# CAN_Breakout.net
KiCad netlist of a schematic drawn in Altium Designer
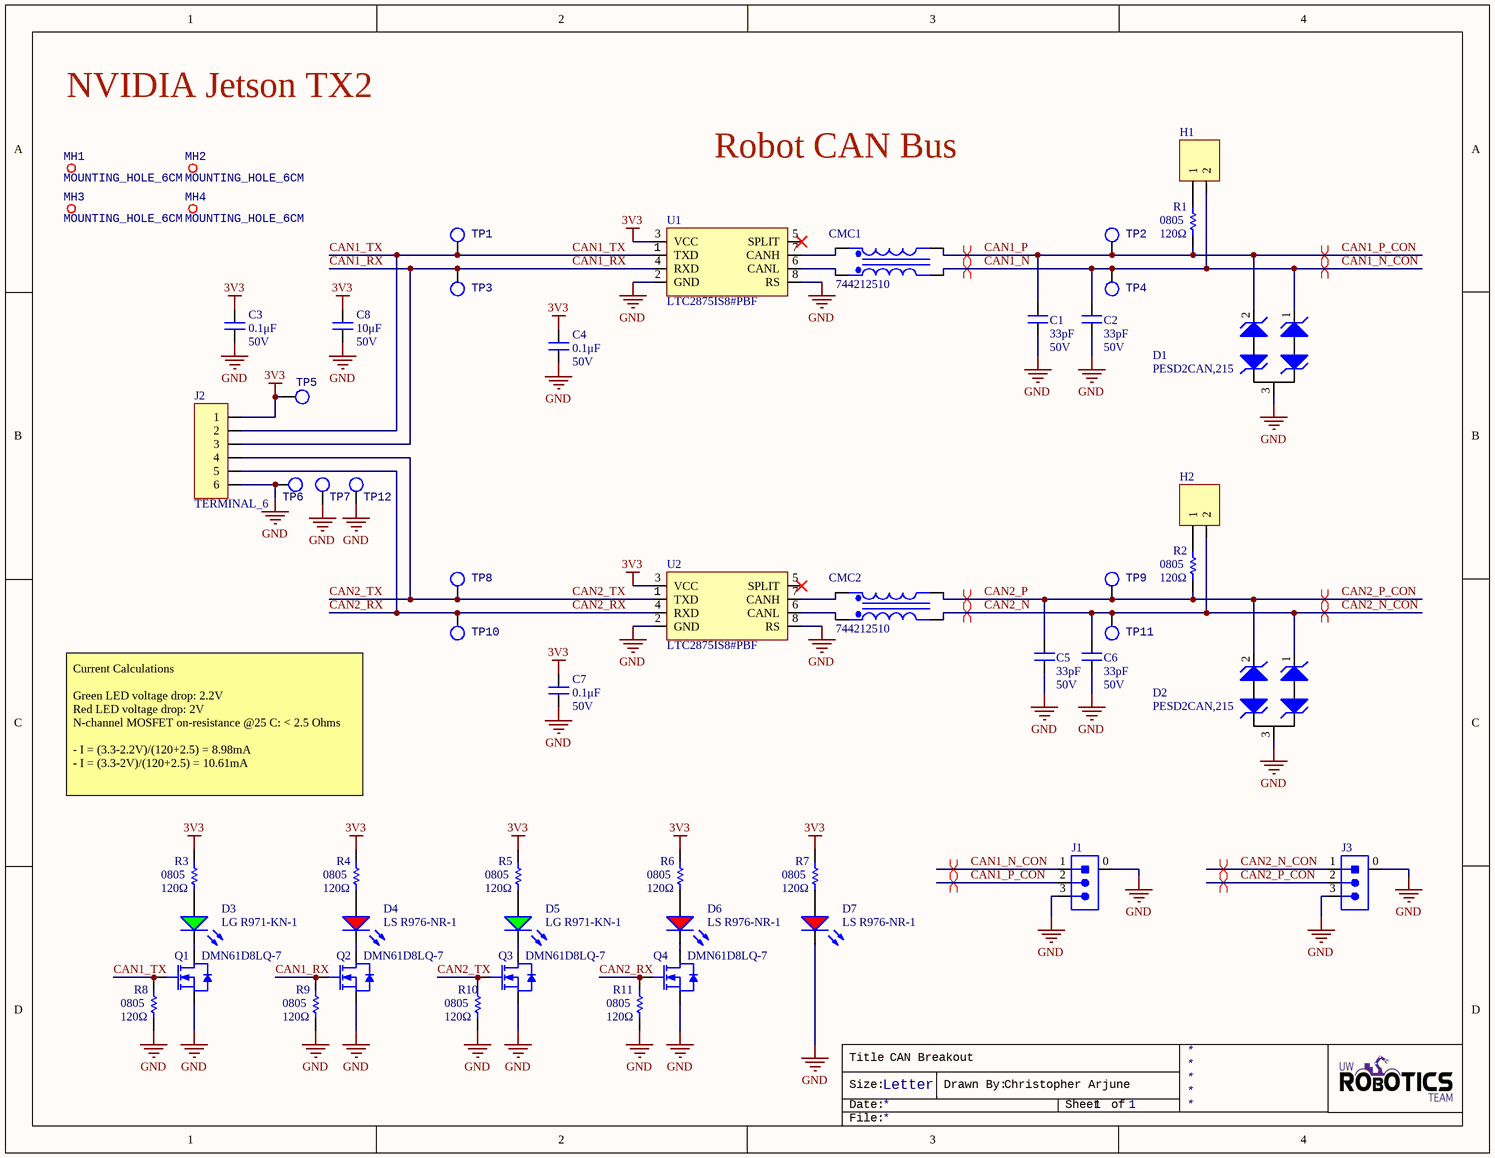
[diagram p0: CAN Breakout.SchDoc]

(export (version "E")
  (design (tool "Eeschema 10.0.6"))
  (components
    (comp (ref "C1")
      (value "33pF")
      (footprint "CAPC0603(1608)55_N")
      (description "CAP CER 33PF 50V C0G/NP0")
      (fields
        (field (name "TOLERANCE") "5%")
        (field (name "VOLTAGE") "50V")
        (field (name "Comment") "CAP_33pF_50V_0603")
      )
      (libsource (lib "UWRT_Schematic_Library_2020") (part "CAP_33pF_50V_0603"))
    )
    (comp (ref "C2")
      (value "33pF")
      (footprint "CAPC0603(1608)55_N")
      (description "CAP CER 33PF 50V C0G/NP0")
      (fields
        (field (name "TOLERANCE") "5%")
        (field (name "VOLTAGE") "50V")
        (field (name "Comment") "CAP_33pF_50V_0603")
      )
      (libsource (lib "UWRT_Schematic_Library_2020") (part "CAP_33pF_50V_0603"))
    )
    (comp (ref "C3")
      (value "0.1μF")
      (footprint "CAPC2012X140N")
      (description "CAP CER 0.1UF 50V X7R 0805")
      (fields (field (name "VOLTAGE RATING") "50V") (field (name "TOLERANCE") "10%"))
      (libsource (lib "UWRT_Schematic_Library_2020") (part "CAP_0.1uF_50V_0805"))
    )
    (comp (ref "C4")
      (value "0.1μF")
      (footprint "CAPC2012X140N")
      (description "CAP CER 0.1UF 50V X7R 0805")
      (fields (field (name "VOLTAGE RATING") "50V") (field (name "TOLERANCE") "10%"))
      (libsource (lib "UWRT_Schematic_Library_2020") (part "CAP_0.1uF_50V_0805"))
    )
    (comp (ref "C5")
      (value "33pF")
      (footprint "CAPC0603(1608)55_N")
      (description "CAP CER 33PF 50V C0G/NP0")
      (fields
        (field (name "TOLERANCE") "5%")
        (field (name "VOLTAGE") "50V")
        (field (name "Comment") "CAP_33pF_50V_0603")
      )
      (libsource (lib "UWRT_Schematic_Library_2020") (part "CAP_33pF_50V_0603"))
    )
    (comp (ref "C6")
      (value "33pF")
      (footprint "CAPC0603(1608)55_N")
      (description "CAP CER 33PF 50V C0G/NP0")
      (fields
        (field (name "TOLERANCE") "5%")
        (field (name "VOLTAGE") "50V")
        (field (name "Comment") "CAP_33pF_50V_0603")
      )
      (libsource (lib "UWRT_Schematic_Library_2020") (part "CAP_33pF_50V_0603"))
    )
    (comp (ref "C7")
      (value "0.1μF")
      (footprint "CAPC2012X140N")
      (description "CAP CER 0.1UF 50V X7R 0805")
      (fields (field (name "VOLTAGE RATING") "50V") (field (name "TOLERANCE") "10%"))
      (libsource (lib "UWRT_Schematic_Library_2020") (part "CAP_0.1uF_50V_0805"))
    )
    (comp (ref "C8")
      (value "10μF")
      (footprint "CAPC1206(3216)")
      (description "CAP CER 10UF 50V X5R 1206")
      (fields (field (name "VOLTAGE RATING") "50V") (field (name "Comment") "10uF"))
      (libsource (lib "UWRT_Schematic_Library_2020") (part "CAP_10uF_50V_1206"))
    )
    (comp (ref "CMC1")
      (value "*")
      (footprint "744212510")
      (description "CMC 51uH 300MA 2LN SMD")
      (fields (field (name "TOLERANCE") "50%") (field (name "MANUFACTURER PART NUMBER 1") "744212510"))
      (libsource (lib "UWRT_Schematic_Library_2020") (part "CMC_51uH"))
    )
    (comp (ref "CMC2")
      (value "*")
      (footprint "744212510")
      (description "CMC 51uH 300MA 2LN SMD")
      (fields (field (name "TOLERANCE") "50%") (field (name "MANUFACTURER PART NUMBER 1") "744212510"))
      (libsource (lib "UWRT_Schematic_Library_2020") (part "CMC_51uH"))
    )
    (comp (ref "D1")
      (value "TVS_DIODE_CAN")
      (footprint "TVS_DIODE_CAN")
      (description "TVS DIODE 24V 41V SOT323-3")
      (fields (field (name "MANUFACTURER PART NUMBER 1") "PESD2CAN,215"))
      (libsource (lib "UWRT_Schematic_Library_2020") (part "TVS_DIODE_CAN"))
    )
    (comp (ref "D2")
      (value "TVS_DIODE_CAN")
      (footprint "TVS_DIODE_CAN")
      (description "TVS DIODE 24V 41V SOT323-3")
      (fields (field (name "MANUFACTURER PART NUMBER 1") "PESD2CAN,215"))
      (libsource (lib "UWRT_Schematic_Library_2020") (part "TVS_DIODE_CAN"))
    )
    (comp (ref "D3")
      (value "LG R971-KN-1")
      (footprint "LED_0805_LINE")
      (description "LED GREEN DIFFUSED 0805 SMD")
      (libsource (lib "UWRT_Schematic_Library_2020") (part "DIO_LED_G"))
    )
    (comp (ref "D4")
      (value "LS R976-NR-1")
      (footprint "LED_0805_LINE")
      (description "LED RED DIFFUSED 0805 SMD")
      (libsource (lib "UWRT_Schematic_Library_2020") (part "DIO_LED_R"))
    )
    (comp (ref "D5")
      (value "LG R971-KN-1")
      (footprint "LED_0805_LINE")
      (description "LED GREEN DIFFUSED 0805 SMD")
      (libsource (lib "UWRT_Schematic_Library_2020") (part "DIO_LED_G"))
    )
    (comp (ref "D6")
      (value "LS R976-NR-1")
      (footprint "LED_0805_LINE")
      (description "LED RED DIFFUSED 0805 SMD")
      (libsource (lib "UWRT_Schematic_Library_2020") (part "DIO_LED_R"))
    )
    (comp (ref "D7")
      (value "LS R976-NR-1")
      (footprint "LED_0805_LINE")
      (description "LED RED DIFFUSED 0805 SMD")
      (libsource (lib "UWRT_Schematic_Library_2020") (part "DIO_LED_R"))
    )
    (comp (ref "H1")
      (value "JUMPER_2")
      (footprint "HDR1X2")
      (description "HEADER 2X1")
      (libsource (lib "UWRT_Schematic_Library_2020") (part "JUMPER_2"))
    )
    (comp (ref "H2")
      (value "JUMPER_2")
      (footprint "HDR1X2")
      (description "HEADER 2X1")
      (libsource (lib "UWRT_Schematic_Library_2020") (part "JUMPER_2"))
    )
    (comp (ref "J1")
      (value "*")
      (footprint "MOLEX-5025850370")
      (description "CONN RCPT 3POS 0.059 TIN SMD R/A")
      (libsource (lib "*") (part "CON_3M_SM_RA"))
    )
    (comp (ref "J2")
      (value "TERMINAL_6")
      (footprint "OSTYK51106030")
      (description "Header, 6-Pin")
      (libsource (lib "UWRT_Schematic_Library_2020") (part "TERMINAL_6"))
    )
    (comp (ref "J3")
      (value "*")
      (footprint "MOLEX-5025850370")
      (description "CONN RCPT 3POS 0.059 TIN SMD R/A")
      (libsource (lib "*") (part "CON_3M_SM_RA"))
    )
    (comp (ref "MH1")
      (value "MOUNTING_HOLE_6CM")
      (footprint "MOUNTING_HOLE")
      (libsource (lib "UWRT_Schematic_Library_2020") (part "MOUNTING_HOLE_6CM"))
    )
    (comp (ref "MH2")
      (value "MOUNTING_HOLE_6CM")
      (footprint "MOUNTING_HOLE")
      (libsource (lib "UWRT_Schematic_Library_2020") (part "MOUNTING_HOLE_6CM"))
    )
    (comp (ref "MH3")
      (value "MOUNTING_HOLE_6CM")
      (footprint "MOUNTING_HOLE")
      (libsource (lib "UWRT_Schematic_Library_2020") (part "MOUNTING_HOLE_6CM"))
    )
    (comp (ref "MH4")
      (value "MOUNTING_HOLE_6CM")
      (footprint "MOUNTING_HOLE")
      (libsource (lib "UWRT_Schematic_Library_2020") (part "MOUNTING_HOLE_6CM"))
    )
    (comp (ref "Q1")
      (value "NMOS_60V_470mA")
      (footprint "SOT23-3")
      (description "MOSFET N-CH 60V SOT23")
      (fields (field (name "MANUFACTURER PART NUMBER 1") "DMN61D8LQ-7"))
      (libsource (lib "UWRT_Schematic_Library_2020") (part "NMOS_60V_470mA"))
    )
    (comp (ref "Q2")
      (value "NMOS_60V_470mA")
      (footprint "SOT23-3")
      (description "MOSFET N-CH 60V SOT23")
      (fields (field (name "MANUFACTURER PART NUMBER 1") "DMN61D8LQ-7"))
      (libsource (lib "UWRT_Schematic_Library_2020") (part "NMOS_60V_470mA"))
    )
    (comp (ref "Q3")
      (value "NMOS_60V_470mA")
      (footprint "SOT23-3")
      (description "MOSFET N-CH 60V SOT23")
      (fields (field (name "MANUFACTURER PART NUMBER 1") "DMN61D8LQ-7"))
      (libsource (lib "UWRT_Schematic_Library_2020") (part "NMOS_60V_470mA"))
    )
    (comp (ref "Q4")
      (value "NMOS_60V_470mA")
      (footprint "SOT23-3")
      (description "MOSFET N-CH 60V SOT23")
      (fields (field (name "MANUFACTURER PART NUMBER 1") "DMN61D8LQ-7"))
      (libsource (lib "UWRT_Schematic_Library_2020") (part "NMOS_60V_470mA"))
    )
    (comp (ref "R1")
      (value "120")
      (footprint "RESC2012X60N")
      (description "RES SMD 120 OHM 1% 1/8W 0805")
      (fields (field (name "CASE CODE (IMPERIAL)") "0805") (field (name "RESISTANCE") "120Ω"))
      (libsource (lib "UWRT_Schematic_Library_2020") (part "RES_120Ω_0805"))
    )
    (comp (ref "R2")
      (value "120")
      (footprint "RESC2012X60N")
      (description "RES SMD 120 OHM 1% 1/8W 0805")
      (fields (field (name "CASE CODE (IMPERIAL)") "0805") (field (name "RESISTANCE") "120Ω"))
      (libsource (lib "UWRT_Schematic_Library_2020") (part "RES_120Ω_0805"))
    )
    (comp (ref "R3")
      (value "120")
      (footprint "RESC2012X60N")
      (description "RES SMD 120 OHM 1% 1/8W 0805")
      (fields (field (name "CASE CODE (IMPERIAL)") "0805") (field (name "RESISTANCE") "120Ω"))
      (libsource (lib "UWRT_Schematic_Library_2020") (part "RES_120Ω_0805"))
    )
    (comp (ref "R4")
      (value "120")
      (footprint "RESC2012X60N")
      (description "RES SMD 120 OHM 1% 1/8W 0805")
      (fields (field (name "CASE CODE (IMPERIAL)") "0805") (field (name "RESISTANCE") "120Ω"))
      (libsource (lib "UWRT_Schematic_Library_2020") (part "RES_120Ω_0805"))
    )
    (comp (ref "R5")
      (value "120")
      (footprint "RESC2012X60N")
      (description "RES SMD 120 OHM 1% 1/8W 0805")
      (fields (field (name "CASE CODE (IMPERIAL)") "0805") (field (name "RESISTANCE") "120Ω"))
      (libsource (lib "UWRT_Schematic_Library_2020") (part "RES_120Ω_0805"))
    )
    (comp (ref "R6")
      (value "120")
      (footprint "RESC2012X60N")
      (description "RES SMD 120 OHM 1% 1/8W 0805")
      (fields (field (name "CASE CODE (IMPERIAL)") "0805") (field (name "RESISTANCE") "120Ω"))
      (libsource (lib "UWRT_Schematic_Library_2020") (part "RES_120Ω_0805"))
    )
    (comp (ref "R7")
      (value "120")
      (footprint "RESC2012X60N")
      (description "RES SMD 120 OHM 1% 1/8W 0805")
      (fields (field (name "CASE CODE (IMPERIAL)") "0805") (field (name "RESISTANCE") "120Ω"))
      (libsource (lib "UWRT_Schematic_Library_2020") (part "RES_120Ω_0805"))
    )
    (comp (ref "R8")
      (value "120")
      (footprint "RESC2012X60N")
      (description "RES SMD 120 OHM 1% 1/8W 0805")
      (fields (field (name "CASE CODE (IMPERIAL)") "0805") (field (name "RESISTANCE") "120Ω"))
      (libsource (lib "UWRT_Schematic_Library_2020") (part "RES_120Ω_0805"))
    )
    (comp (ref "R9")
      (value "120")
      (footprint "RESC2012X60N")
      (description "RES SMD 120 OHM 1% 1/8W 0805")
      (fields (field (name "CASE CODE (IMPERIAL)") "0805") (field (name "RESISTANCE") "120Ω"))
      (libsource (lib "UWRT_Schematic_Library_2020") (part "RES_120Ω_0805"))
    )
    (comp (ref "R10")
      (value "120")
      (footprint "RESC2012X60N")
      (description "RES SMD 120 OHM 1% 1/8W 0805")
      (fields (field (name "CASE CODE (IMPERIAL)") "0805") (field (name "RESISTANCE") "120Ω"))
      (libsource (lib "UWRT_Schematic_Library_2020") (part "RES_120Ω_0805"))
    )
    (comp (ref "R11")
      (value "120")
      (footprint "RESC2012X60N")
      (description "RES SMD 120 OHM 1% 1/8W 0805")
      (fields (field (name "CASE CODE (IMPERIAL)") "0805") (field (name "RESISTANCE") "120Ω"))
      (libsource (lib "UWRT_Schematic_Library_2020") (part "RES_120Ω_0805"))
    )
    (comp (ref "TP1")
      (value "TESTPOINT_LOOP")
      (footprint "TESTPOINT_LOOP")
      (description "PC TEST POINT MINIATURE WHITE")
      (libsource (lib "UWRT_Schematic_Library_2020") (part "TESTPOINT_LOOP"))
    )
    (comp (ref "TP2")
      (value "TESTPOINT_LOOP")
      (footprint "TESTPOINT_LOOP")
      (description "PC TEST POINT MINIATURE WHITE")
      (libsource (lib "UWRT_Schematic_Library_2020") (part "TESTPOINT_LOOP"))
    )
    (comp (ref "TP3")
      (value "TESTPOINT_LOOP")
      (footprint "TESTPOINT_LOOP")
      (description "PC TEST POINT MINIATURE WHITE")
      (libsource (lib "UWRT_Schematic_Library_2020") (part "TESTPOINT_LOOP"))
    )
    (comp (ref "TP4")
      (value "TESTPOINT_LOOP")
      (footprint "TESTPOINT_LOOP")
      (description "PC TEST POINT MINIATURE WHITE")
      (libsource (lib "UWRT_Schematic_Library_2020") (part "TESTPOINT_LOOP"))
    )
    (comp (ref "TP5")
      (value "TESTPOINT_LOOP")
      (footprint "TESTPOINT_LOOP")
      (description "PC TEST POINT MINIATURE WHITE")
      (libsource (lib "UWRT_Schematic_Library_2020") (part "TESTPOINT_LOOP"))
    )
    (comp (ref "TP6")
      (value "TESTPOINT_LOOP")
      (footprint "TESTPOINT_LOOP")
      (description "PC TEST POINT MINIATURE WHITE")
      (libsource (lib "UWRT_Schematic_Library_2020") (part "TESTPOINT_LOOP"))
    )
    (comp (ref "TP7")
      (value "TESTPOINT_LOOP")
      (footprint "TESTPOINT_LOOP")
      (description "PC TEST POINT MINIATURE WHITE")
      (libsource (lib "UWRT_Schematic_Library_2020") (part "TESTPOINT_LOOP"))
    )
    (comp (ref "TP8")
      (value "TESTPOINT_LOOP")
      (footprint "TESTPOINT_LOOP")
      (description "PC TEST POINT MINIATURE WHITE")
      (libsource (lib "UWRT_Schematic_Library_2020") (part "TESTPOINT_LOOP"))
    )
    (comp (ref "TP9")
      (value "TESTPOINT_LOOP")
      (footprint "TESTPOINT_LOOP")
      (description "PC TEST POINT MINIATURE WHITE")
      (libsource (lib "UWRT_Schematic_Library_2020") (part "TESTPOINT_LOOP"))
    )
    (comp (ref "TP10")
      (value "TESTPOINT_LOOP")
      (footprint "TESTPOINT_LOOP")
      (description "PC TEST POINT MINIATURE WHITE")
      (libsource (lib "UWRT_Schematic_Library_2020") (part "TESTPOINT_LOOP"))
    )
    (comp (ref "TP11")
      (value "TESTPOINT_LOOP")
      (footprint "TESTPOINT_LOOP")
      (description "PC TEST POINT MINIATURE WHITE")
      (libsource (lib "UWRT_Schematic_Library_2020") (part "TESTPOINT_LOOP"))
    )
    (comp (ref "TP12")
      (value "TESTPOINT_LOOP")
      (footprint "TESTPOINT_LOOP")
      (description "PC TEST POINT MINIATURE WHITE")
      (libsource (lib "UWRT_Schematic_Library_2020") (part "TESTPOINT_LOOP"))
    )
    (comp (ref "U1")
      (value "IC TXRX CAN")
      (footprint "LT-S8_N")
      (description "IC TXRX CAN 4MBPS 8SO")
      (fields (field (name "MANUFACTURER PART NUMBER 1") "LTC2875IS8#PBF"))
      (libsource (lib "UWRT_Schematic_Library_2020") (part "LTC2875"))
    )
    (comp (ref "U2")
      (value "IC TXRX CAN")
      (footprint "LT-S8_N")
      (description "IC TXRX CAN 4MBPS 8SO")
      (fields (field (name "MANUFACTURER PART NUMBER 1") "LTC2875IS8#PBF"))
      (libsource (lib "UWRT_Schematic_Library_2020") (part "LTC2875"))
    )
  )
  (nets
    (net (code "1") (name "/CAN1_N") (class "Default")
      (node (ref "C2") (pin "2") (pinfunction "2_2") (pintype "passive"))
      (node (ref "CMC1") (pin "5") (pinfunction "Pri-_5") (pintype "passive"))
      (node (ref "D1") (pin "1") (pinfunction "1_1") (pintype "passive"))
      (node (ref "H1") (pin "2") (pinfunction "2_2") (pintype "passive"))
      (node (ref "J1") (pin "1") (pinfunction "1_1") (pintype "passive"))
      (node (ref "TP4") (pin "1") (pintype "passive"))
    )
    (net (code "2") (name "/CAN1_P") (class "Default")
      (node (ref "C1") (pin "2") (pinfunction "2_2") (pintype "passive"))
      (node (ref "CMC1") (pin "4") (pinfunction "Sec-_4") (pintype "passive"))
      (node (ref "D1") (pin "2") (pinfunction "2_2") (pintype "passive"))
      (node (ref "J1") (pin "2") (pinfunction "2_2") (pintype "passive"))
      (node (ref "R1") (pin "1") (pinfunction "1_1") (pintype "passive"))
      (node (ref "TP2") (pin "1") (pintype "passive"))
    )
    (net (code "3") (name "/CAN1_RX") (class "Default")
      (node (ref "J2") (pin "3") (pinfunction "3_3") (pintype "passive"))
      (node (ref "Q2") (pin "1") (pinfunction "GATE_1") (pintype "passive"))
      (node (ref "R9") (pin "2") (pinfunction "2_2") (pintype "passive"))
      (node (ref "TP3") (pin "1") (pintype "passive"))
      (node (ref "U1") (pin "4") (pinfunction "RXD_4") (pintype "passive"))
    )
    (net (code "4") (name "/CAN1_TX") (class "Default")
      (node (ref "J2") (pin "2") (pinfunction "2_2") (pintype "passive"))
      (node (ref "Q1") (pin "1") (pinfunction "GATE_1") (pintype "passive"))
      (node (ref "R8") (pin "2") (pinfunction "2_2") (pintype "passive"))
      (node (ref "TP1") (pin "1") (pintype "passive"))
      (node (ref "U1") (pin "1") (pinfunction "TXD_1") (pintype "passive"))
    )
    (net (code "5") (name "/CAN2_N") (class "Default")
      (node (ref "C6") (pin "2") (pinfunction "2_2") (pintype "passive"))
      (node (ref "CMC2") (pin "5") (pinfunction "Pri-_5") (pintype "passive"))
      (node (ref "D2") (pin "1") (pinfunction "1_1") (pintype "passive"))
      (node (ref "H2") (pin "2") (pinfunction "2_2") (pintype "passive"))
      (node (ref "J3") (pin "1") (pinfunction "1_1") (pintype "passive"))
      (node (ref "TP11") (pin "1") (pintype "passive"))
    )
    (net (code "6") (name "/CAN2_P") (class "Default")
      (node (ref "C5") (pin "2") (pinfunction "2_2") (pintype "passive"))
      (node (ref "CMC2") (pin "4") (pinfunction "Sec-_4") (pintype "passive"))
      (node (ref "D2") (pin "2") (pinfunction "2_2") (pintype "passive"))
      (node (ref "J3") (pin "2") (pinfunction "2_2") (pintype "passive"))
      (node (ref "R2") (pin "1") (pinfunction "1_1") (pintype "passive"))
      (node (ref "TP9") (pin "1") (pintype "passive"))
    )
    (net (code "7") (name "/CAN2_RX") (class "Default")
      (node (ref "J2") (pin "5") (pinfunction "5_5") (pintype "passive"))
      (node (ref "Q4") (pin "1") (pinfunction "GATE_1") (pintype "passive"))
      (node (ref "R11") (pin "2") (pinfunction "2_2") (pintype "passive"))
      (node (ref "TP10") (pin "1") (pintype "passive"))
      (node (ref "U2") (pin "4") (pinfunction "RXD_4") (pintype "passive"))
    )
    (net (code "8") (name "/CAN2_TX") (class "Default")
      (node (ref "J2") (pin "4") (pinfunction "4_4") (pintype "passive"))
      (node (ref "Q3") (pin "1") (pinfunction "GATE_1") (pintype "passive"))
      (node (ref "R10") (pin "2") (pinfunction "2_2") (pintype "passive"))
      (node (ref "TP8") (pin "1") (pintype "passive"))
      (node (ref "U2") (pin "1") (pinfunction "TXD_1") (pintype "passive"))
    )
    (net (code "9") (name "3V3") (class "Default")
      (node (ref "C3") (pin "2") (pinfunction "2_2") (pintype "passive"))
      (node (ref "C4") (pin "2") (pinfunction "2_2") (pintype "passive"))
      (node (ref "C7") (pin "2") (pinfunction "2_2") (pintype "passive"))
      (node (ref "C8") (pin "2") (pinfunction "2_2") (pintype "passive"))
      (node (ref "J2") (pin "1") (pinfunction "1_1") (pintype "passive"))
      (node (ref "R3") (pin "2") (pinfunction "2_2") (pintype "passive"))
      (node (ref "R4") (pin "2") (pinfunction "2_2") (pintype "passive"))
      (node (ref "R5") (pin "2") (pinfunction "2_2") (pintype "passive"))
      (node (ref "R6") (pin "2") (pinfunction "2_2") (pintype "passive"))
      (node (ref "R7") (pin "2") (pinfunction "2_2") (pintype "passive"))
      (node (ref "TP5") (pin "1") (pintype "passive"))
      (node (ref "U1") (pin "3") (pinfunction "VCC_3") (pintype "passive"))
      (node (ref "U2") (pin "3") (pinfunction "VCC_3") (pintype "passive"))
    )
    (net (code "10") (name "GND") (class "Default")
      (node (ref "C1") (pin "1") (pinfunction "1_1") (pintype "passive"))
      (node (ref "C2") (pin "1") (pinfunction "1_1") (pintype "passive"))
      (node (ref "C3") (pin "1") (pinfunction "1_1") (pintype "passive"))
      (node (ref "C4") (pin "1") (pinfunction "1_1") (pintype "passive"))
      (node (ref "C5") (pin "1") (pinfunction "1_1") (pintype "passive"))
      (node (ref "C6") (pin "1") (pinfunction "1_1") (pintype "passive"))
      (node (ref "C7") (pin "1") (pinfunction "1_1") (pintype "passive"))
      (node (ref "C8") (pin "1") (pinfunction "1_1") (pintype "passive"))
      (node (ref "D1") (pin "3") (pinfunction "3_3") (pintype "passive"))
      (node (ref "D2") (pin "3") (pinfunction "3_3") (pintype "passive"))
      (node (ref "D7") (pin "2") (pinfunction "K_2") (pintype "passive"))
      (node (ref "J1") (pin "0") (pinfunction "0_0") (pintype "passive"))
      (node (ref "J1") (pin "3") (pinfunction "3_3") (pintype "passive"))
      (node (ref "J2") (pin "6") (pinfunction "6_6") (pintype "passive"))
      (node (ref "J3") (pin "0") (pinfunction "0_0") (pintype "passive"))
      (node (ref "J3") (pin "3") (pinfunction "3_3") (pintype "passive"))
      (node (ref "Q1") (pin "2") (pinfunction "SOURCE_2") (pintype "passive"))
      (node (ref "Q2") (pin "2") (pinfunction "SOURCE_2") (pintype "passive"))
      (node (ref "Q3") (pin "2") (pinfunction "SOURCE_2") (pintype "passive"))
      (node (ref "Q4") (pin "2") (pinfunction "SOURCE_2") (pintype "passive"))
      (node (ref "R10") (pin "1") (pinfunction "1_1") (pintype "passive"))
      (node (ref "R11") (pin "1") (pinfunction "1_1") (pintype "passive"))
      (node (ref "R8") (pin "1") (pinfunction "1_1") (pintype "passive"))
      (node (ref "R9") (pin "1") (pinfunction "1_1") (pintype "passive"))
      (node (ref "TP12") (pin "1") (pintype "passive"))
      (node (ref "TP6") (pin "1") (pintype "passive"))
      (node (ref "TP7") (pin "1") (pintype "passive"))
      (node (ref "U1") (pin "2") (pinfunction "GND_2") (pintype "passive"))
      (node (ref "U1") (pin "8") (pinfunction "RS_8") (pintype "passive"))
      (node (ref "U2") (pin "2") (pinfunction "GND_2") (pintype "passive"))
      (node (ref "U2") (pin "8") (pinfunction "RS_8") (pintype "passive"))
    )
    (net (code "11") (name "Net-(CMC1-Pri+)") (class "Default")
      (node (ref "CMC1") (pin "1") (pinfunction "Pri+_1") (pintype "passive"))
      (node (ref "U1") (pin "6") (pinfunction "CANL_6") (pintype "passive"))
    )
    (net (code "12") (name "Net-(CMC1-Sec+)") (class "Default")
      (node (ref "CMC1") (pin "3") (pinfunction "Sec+_3") (pintype "passive"))
      (node (ref "U1") (pin "7") (pinfunction "CANH_7") (pintype "passive"))
    )
    (net (code "13") (name "Net-(CMC2-Pri+)") (class "Default")
      (node (ref "CMC2") (pin "1") (pinfunction "Pri+_1") (pintype "passive"))
      (node (ref "U2") (pin "6") (pinfunction "CANL_6") (pintype "passive"))
    )
    (net (code "14") (name "Net-(CMC2-Sec+)") (class "Default")
      (node (ref "CMC2") (pin "3") (pinfunction "Sec+_3") (pintype "passive"))
      (node (ref "U2") (pin "7") (pinfunction "CANH_7") (pintype "passive"))
    )
    (net (code "15") (name "Net-(D3-A)") (class "Default")
      (node (ref "D3") (pin "1") (pinfunction "A_1") (pintype "passive"))
      (node (ref "R3") (pin "1") (pinfunction "1_1") (pintype "passive"))
    )
    (net (code "16") (name "Net-(D3-K)") (class "Default")
      (node (ref "D3") (pin "2") (pinfunction "K_2") (pintype "passive"))
      (node (ref "Q1") (pin "3") (pinfunction "DRAIN_3") (pintype "passive"))
    )
    (net (code "17") (name "Net-(D4-A)") (class "Default")
      (node (ref "D4") (pin "1") (pinfunction "A_1") (pintype "passive"))
      (node (ref "R4") (pin "1") (pinfunction "1_1") (pintype "passive"))
    )
    (net (code "18") (name "Net-(D4-K)") (class "Default")
      (node (ref "D4") (pin "2") (pinfunction "K_2") (pintype "passive"))
      (node (ref "Q2") (pin "3") (pinfunction "DRAIN_3") (pintype "passive"))
    )
    (net (code "19") (name "Net-(D5-A)") (class "Default")
      (node (ref "D5") (pin "1") (pinfunction "A_1") (pintype "passive"))
      (node (ref "R5") (pin "1") (pinfunction "1_1") (pintype "passive"))
    )
    (net (code "20") (name "Net-(D5-K)") (class "Default")
      (node (ref "D5") (pin "2") (pinfunction "K_2") (pintype "passive"))
      (node (ref "Q3") (pin "3") (pinfunction "DRAIN_3") (pintype "passive"))
    )
    (net (code "21") (name "Net-(D6-A)") (class "Default")
      (node (ref "D6") (pin "1") (pinfunction "A_1") (pintype "passive"))
      (node (ref "R6") (pin "1") (pinfunction "1_1") (pintype "passive"))
    )
    (net (code "22") (name "Net-(D6-K)") (class "Default")
      (node (ref "D6") (pin "2") (pinfunction "K_2") (pintype "passive"))
      (node (ref "Q4") (pin "3") (pinfunction "DRAIN_3") (pintype "passive"))
    )
    (net (code "23") (name "Net-(D7-A)") (class "Default")
      (node (ref "D7") (pin "1") (pinfunction "A_1") (pintype "passive"))
      (node (ref "R7") (pin "1") (pinfunction "1_1") (pintype "passive"))
    )
    (net (code "24") (name "Net-(H1-Pad1)") (class "Default")
      (node (ref "H1") (pin "1") (pinfunction "1_1") (pintype "passive"))
      (node (ref "R1") (pin "2") (pinfunction "2_2") (pintype "passive"))
    )
    (net (code "25") (name "Net-(H2-Pad1)") (class "Default")
      (node (ref "H2") (pin "1") (pinfunction "1_1") (pintype "passive"))
      (node (ref "R2") (pin "2") (pinfunction "2_2") (pintype "passive"))
    )
    (net (code "26") (name "unconnected-(U1-SPLIT-Pad5)") (class "Default")
      (node (ref "U1") (pin "5") (pinfunction "SPLIT_5") (pintype "passive+no_connect"))
    )
    (net (code "27") (name "unconnected-(U2-SPLIT-Pad5)") (class "Default")
      (node (ref "U2") (pin "5") (pinfunction "SPLIT_5") (pintype "passive+no_connect"))
    )
  )
)
